# charger.net
KiCad netlist of a schematic drawn in Altium Designer
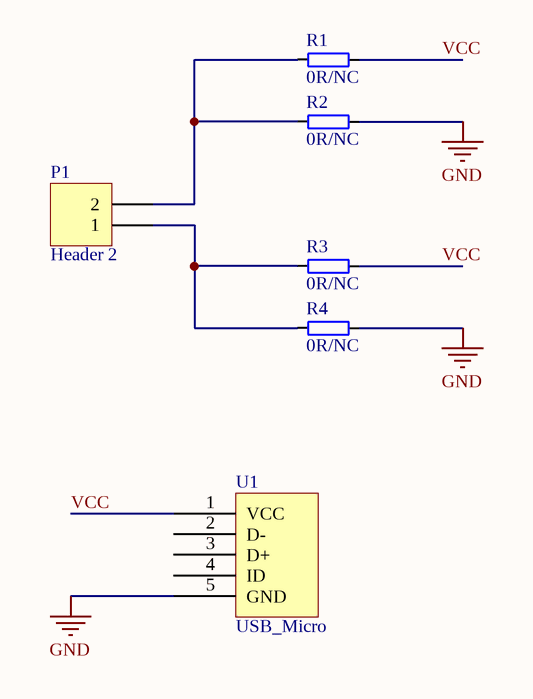
[diagram p0: charger.SchDoc]

(export (version "E")
  (design (tool "Eeschema 10.0.6"))
  (components
    (comp (ref "P1")
      (value "Header 2")
      (footprint "USB_PIN-2")
      (description "Header, 2-Pin")
      (fields (field (name "PUBLISHER") "Altium Limited"))
      (libsource (lib "Miscellaneous Connectors") (part "Header 2"))
    )
    (comp (ref "R1")
      (value "0R/NC")
      (footprint "PCB1:0603-1")
      (description "resistor")
      (libsource (lib "PCB_Project1") (part "R-10K"))
    )
    (comp (ref "R2")
      (value "0R/NC")
      (footprint "0603-1")
      (description "resistor")
      (libsource (lib "PCB_Project1") (part "R-10K"))
    )
    (comp (ref "R3")
      (value "0R/NC")
      (footprint "0603-1")
      (description "resistor")
      (libsource (lib "PCB_Project1") (part "R-10K"))
    )
    (comp (ref "R4")
      (value "0R/NC")
      (footprint "0603-1")
      (description "resistor")
      (libsource (lib "PCB_Project1") (part "R-10K"))
    )
    (comp (ref "U1")
      (value "USB_Micro")
      (footprint "usb_micro")
      (libsource (lib "PCB_Project1") (part "USB_Micro"))
    )
  )
  (nets
    (net (code "1") (name "/VCC") (class "Default")
      (node (ref "R1") (pin "2") (pinfunction "2_2") (pintype "passive"))
      (node (ref "R3") (pin "2") (pinfunction "2_2") (pintype "passive"))
      (node (ref "U1") (pin "1") (pinfunction "VCC_1") (pintype "passive"))
    )
    (net (code "2") (name "GND") (class "Default")
      (node (ref "R2") (pin "2") (pinfunction "2_2") (pintype "passive"))
      (node (ref "R4") (pin "2") (pinfunction "2_2") (pintype "passive"))
      (node (ref "U1") (pin "5") (pinfunction "GND_5") (pintype "passive"))
    )
    (net (code "3") (name "Net-(P1-Pad1)") (class "Default")
      (node (ref "P1") (pin "1") (pinfunction "1_1") (pintype "passive"))
      (node (ref "R3") (pin "1") (pinfunction "1_1") (pintype "passive"))
      (node (ref "R4") (pin "1") (pinfunction "1_1") (pintype "passive"))
    )
    (net (code "4") (name "Net-(P1-Pad2)") (class "Default")
      (node (ref "P1") (pin "2") (pinfunction "2_2") (pintype "passive"))
      (node (ref "R1") (pin "1") (pinfunction "1_1") (pintype "passive"))
      (node (ref "R2") (pin "1") (pinfunction "1_1") (pintype "passive"))
    )
    (net (code "5") (name "unconnected-(U1-D+-Pad3)") (class "Default")
      (node (ref "U1") (pin "3") (pinfunction "D+_3") (pintype "passive"))
    )
    (net (code "6") (name "unconnected-(U1-D--Pad2)") (class "Default")
      (node (ref "U1") (pin "2") (pinfunction "D-_2") (pintype "passive"))
    )
    (net (code "7") (name "unconnected-(U1-ID-Pad4)") (class "Default")
      (node (ref "U1") (pin "4") (pinfunction "ID_4") (pintype "passive"))
    )
  )
)
